# 02_ESP12_CORE.net
KiCad netlist of a schematic drawn in Altium Designer
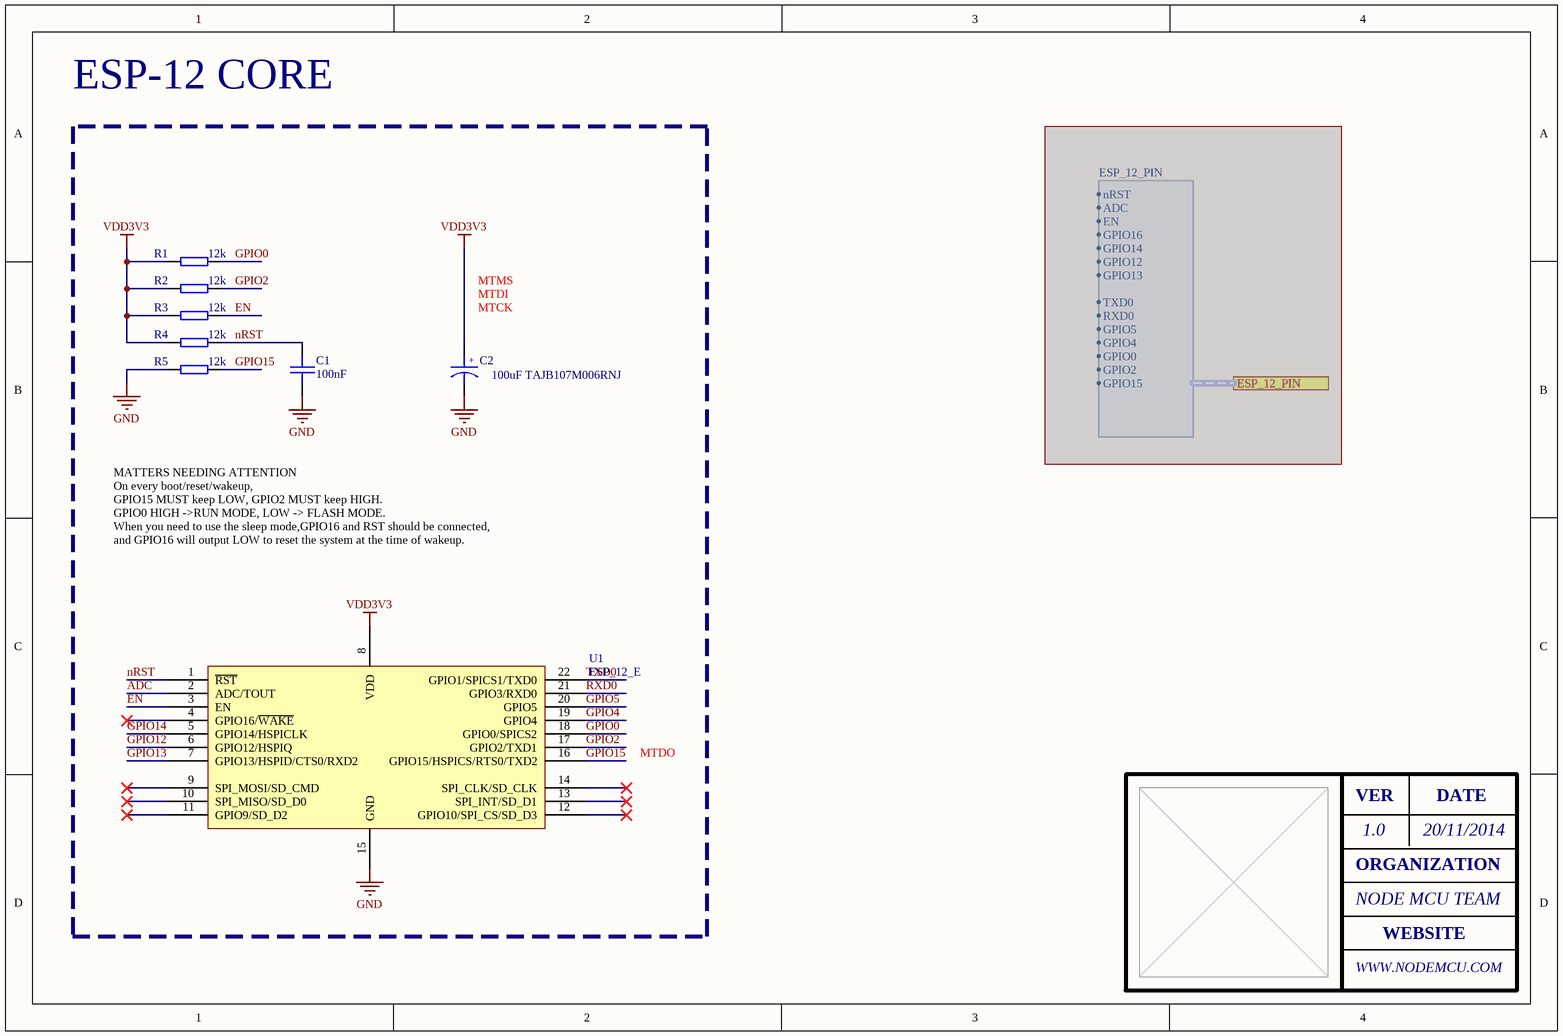
[diagram p0: 02_ESP12_CORE.SchDoc]

(export (version "E")
  (design (tool "Eeschema 10.0.6"))
  (components
    (comp (ref "C1")
      (value "100nF")
      (footprint "SMT_C_0402")
      (description "Surface mount capacitor 0402")
      (libsource (lib "cupmat") (part "SMT_C_0402"))
    )
    (comp (ref "C2")
      (value "100uF TAJB107M006RNJ")
      (footprint "SMT_C_Tantalum_B")
      (description "Capacitor, SM Tantalum; Body 3.5 x 2.8 mm (LxW typ)")
      (libsource (lib "cupmat") (part "SMT_C_Tantalum_B"))
    )
    (comp (ref "R1")
      (value "12k")
      (footprint "SMT_R_0402")
      (description "Surface mount resistor 0402")
      (libsource (lib "cupmat") (part "SMT_R_0402"))
    )
    (comp (ref "R2")
      (value "12k")
      (footprint "SMT_R_0402")
      (description "Surface mount resistor 0402")
      (libsource (lib "cupmat") (part "SMT_R_0402"))
    )
    (comp (ref "R3")
      (value "12k")
      (footprint "SMT_R_0402")
      (description "Surface mount resistor 0402")
      (libsource (lib "cupmat") (part "SMT_R_0402"))
    )
    (comp (ref "R4")
      (value "12k")
      (footprint "SMT_R_0402")
      (description "Surface mount resistor 0402")
      (libsource (lib "cupmat") (part "SMT_R_0402"))
    )
    (comp (ref "R5")
      (value "12k")
      (footprint "SMT_R_0402")
      (description "Surface mount resistor 0402")
      (libsource (lib "cupmat") (part "SMT_R_0402"))
    )
    (comp (ref "U1")
      (value "ESP_12_E")
      (footprint "ESP_12_E")
      (description "ESP-12 Wi-Fi Module by AI-Thinker")
      (libsource (lib "cupmat") (part "ESP_12_E"))
    )
  )
  (nets
    (net (code "2") (name "/ADC") (class "Default")
      (node (ref "U1") (pin "2") (pinfunction "ADC/TOUT_2") (pintype "passive"))
    )
    (net (code "3") (name "/EN") (class "Default")
      (node (ref "R3") (pin "2") (pinfunction "2_2") (pintype "passive"))
      (node (ref "U1") (pin "3") (pinfunction "EN_3") (pintype "passive"))
    )
    (net (code "4") (name "/GPIO0") (class "Default")
      (node (ref "R1") (pin "2") (pinfunction "2_2") (pintype "passive"))
      (node (ref "U1") (pin "18") (pinfunction "GPIO0/SPICS2_18") (pintype "passive"))
    )
    (net (code "5") (name "/GPIO2") (class "Default")
      (node (ref "R2") (pin "2") (pinfunction "2_2") (pintype "passive"))
      (node (ref "U1") (pin "17") (pinfunction "GPIO2/TXD1_17") (pintype "passive"))
    )
    (net (code "6") (name "/GPIO4") (class "Default")
      (node (ref "U1") (pin "19") (pinfunction "GPIO4_19") (pintype "passive"))
    )
    (net (code "7") (name "/GPIO5") (class "Default")
      (node (ref "U1") (pin "20") (pinfunction "GPIO5_20") (pintype "passive"))
    )
    (net (code "8") (name "/GPIO12") (class "Default")
      (node (ref "U1") (pin "6") (pinfunction "GPIO12/HSPIQ_6") (pintype "passive"))
    )
    (net (code "9") (name "/GPIO13") (class "Default")
      (node (ref "U1") (pin "7") (pinfunction "GPIO13/HSPID/CTS0/RXD2_7") (pintype "passive"))
    )
    (net (code "10") (name "/GPIO14") (class "Default")
      (node (ref "U1") (pin "5") (pinfunction "GPIO14/HSPICLK_5") (pintype "passive"))
    )
    (net (code "11") (name "/GPIO15") (class "Default")
      (node (ref "R5") (pin "2") (pinfunction "2_2") (pintype "passive"))
      (node (ref "U1") (pin "16") (pinfunction "GPIO15/HSPICS/RTS0/TXD2_16") (pintype "passive"))
    )
    (net (code "12") (name "/RXD0") (class "Default")
      (node (ref "U1") (pin "21") (pinfunction "GPIO3/RXD0_21") (pintype "passive"))
    )
    (net (code "13") (name "/TXD0") (class "Default")
      (node (ref "U1") (pin "22") (pinfunction "GPIO1/SPICS1/TXD0_22") (pintype "passive"))
    )
    (net (code "14") (name "/nRST") (class "Default")
      (node (ref "C1") (pin "1") (pinfunction "1_1") (pintype "passive"))
      (node (ref "R4") (pin "2") (pinfunction "2_2") (pintype "passive"))
      (node (ref "U1") (pin "1") (pinfunction "~{RST}_1") (pintype "passive"))
    )
    (net (code "16") (name "GND") (class "Default")
      (node (ref "C1") (pin "2") (pinfunction "2_2") (pintype "passive"))
      (node (ref "C2") (pin "2") (pinfunction "2_2") (pintype "passive"))
      (node (ref "R5") (pin "1") (pinfunction "1_1") (pintype "passive"))
      (node (ref "U1") (pin "15") (pinfunction "GND_15") (pintype "passive"))
    )
    (net (code "17") (name "VDD3V3") (class "Default")
      (node (ref "C2") (pin "1") (pinfunction "1_1") (pintype "passive"))
      (node (ref "R1") (pin "1") (pinfunction "1_1") (pintype "passive"))
      (node (ref "R2") (pin "1") (pinfunction "1_1") (pintype "passive"))
      (node (ref "R3") (pin "1") (pinfunction "1_1") (pintype "passive"))
      (node (ref "R4") (pin "1") (pinfunction "1_1") (pintype "passive"))
      (node (ref "U1") (pin "8") (pinfunction "VDD_8") (pintype "passive"))
    )
    (net (code "18") (name "unconnected-(U1-GPIO9{slash}SD_D2-Pad11)") (class "Default")
      (node (ref "U1") (pin "11") (pinfunction "GPIO9/SD_D2_11") (pintype "passive+no_connect"))
    )
    (net (code "19") (name "unconnected-(U1-GPIO10{slash}SPI_CS{slash}SD_D3-Pad12)") (class "Default")
      (node (ref "U1") (pin "12") (pinfunction "GPIO10/SPI_CS/SD_D3_12") (pintype "passive+no_connect"))
    )
    (net (code "20") (name "unconnected-(U1-GPIO16{slash}~{WAKE}-Pad4)") (class "Default")
      (node (ref "U1") (pin "4") (pinfunction "GPIO16/~{WAKE}_4") (pintype "passive+no_connect"))
    )
    (net (code "21") (name "unconnected-(U1-SPI_CLK{slash}SD_CLK-Pad14)") (class "Default")
      (node (ref "U1") (pin "14") (pinfunction "SPI_CLK/SD_CLK_14") (pintype "passive+no_connect"))
    )
    (net (code "22") (name "unconnected-(U1-SPI_INT{slash}SD_D1-Pad13)") (class "Default")
      (node (ref "U1") (pin "13") (pinfunction "SPI_INT/SD_D1_13") (pintype "passive+no_connect"))
    )
    (net (code "23") (name "unconnected-(U1-SPI_MISO{slash}SD_D0-Pad10)") (class "Default")
      (node (ref "U1") (pin "10") (pinfunction "SPI_MISO/SD_D0_10") (pintype "passive+no_connect"))
    )
    (net (code "24") (name "unconnected-(U1-SPI_MOSI{slash}SD_CMD-Pad9)") (class "Default")
      (node (ref "U1") (pin "9") (pinfunction "SPI_MOSI/SD_CMD_9") (pintype "passive+no_connect"))
    )
  )
)
